# MSP430FR2433_SMD_0402.net
KiCad netlist of a schematic drawn in EAGLE
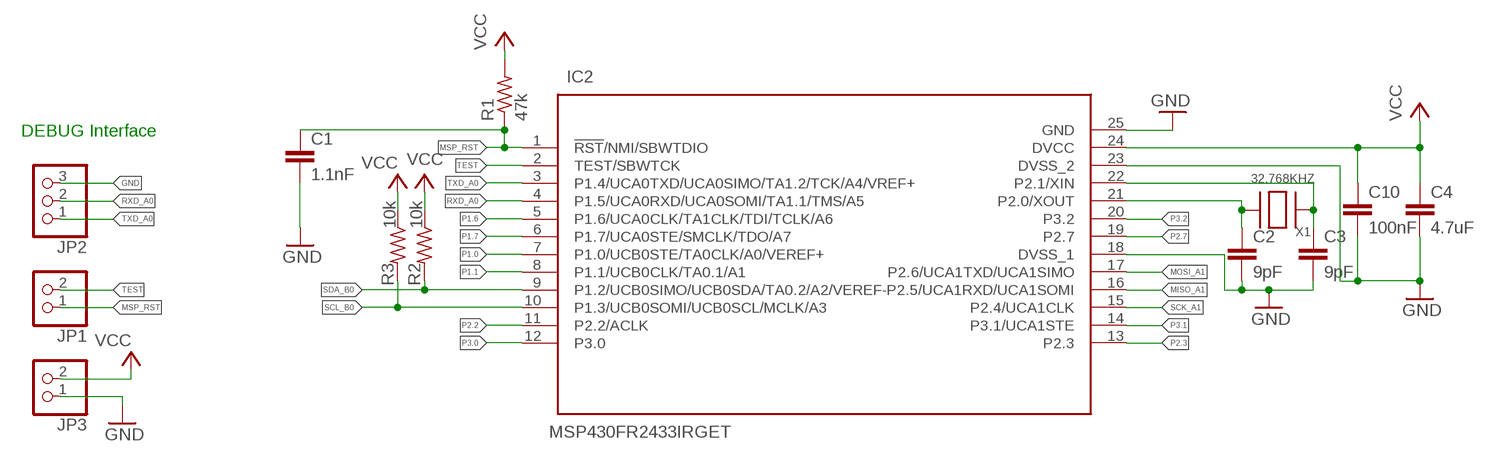
[diagram p0: schematic, sheet 1]

(export (version "E")
  (design (tool "Eeschema 10.0.6"))
  (components
    (comp (ref "C1")
      (value "1.1nF")
      (footprint "eagle-import:C0402")
      (libsource (lib "eagle-import") (part "C-EUC0402"))
    )
    (comp (ref "C2")
      (value "9pF")
      (footprint "eagle-import:C0402")
      (libsource (lib "eagle-import") (part "C-EUC0402"))
    )
    (comp (ref "C3")
      (value "9pF")
      (footprint "eagle-import:C0402")
      (libsource (lib "eagle-import") (part "C-EUC0402"))
    )
    (comp (ref "C4")
      (value "4.7uF")
      (footprint "eagle-import:C0402")
      (libsource (lib "eagle-import") (part "C-EUC0402"))
    )
    (comp (ref "C10")
      (value "100nF")
      (footprint "eagle-import:C0402")
      (libsource (lib "eagle-import") (part "C-EUC0402"))
    )
    (comp (ref "IC2")
      (value "MSP430FR2433IRGET")
      (footprint "eagle-import:QFN50P400X400X100-25N")
      (fields (field (name "MOUSER_PART_NUMBER") "595-SP430FR2433IRGET"))
      (libsource (lib "eagle-import") (part "MSP430FR2433IRGET"))
    )
    (comp (ref "JP1")
      (value "PINHD-1X2")
      (footprint "eagle-import:1X02")
      (libsource (lib "eagle-import") (part "PINHD-1X2"))
    )
    (comp (ref "JP2")
      (value "PINHD-1X3")
      (footprint "eagle-import:1X03")
      (libsource (lib "eagle-import") (part "PINHD-1X3"))
    )
    (comp (ref "JP3")
      (value "PINHD-1X2")
      (footprint "eagle-import:1X02")
      (libsource (lib "eagle-import") (part "PINHD-1X2"))
    )
    (comp (ref "R1")
      (value "47k")
      (footprint "eagle-import:R0402")
      (libsource (lib "eagle-import") (part "R-US_R0402"))
    )
    (comp (ref "R2")
      (value "10k")
      (footprint "eagle-import:R0402")
      (libsource (lib "eagle-import") (part "R-US_R0402"))
    )
    (comp (ref "R3")
      (value "10k")
      (footprint "eagle-import:R0402")
      (libsource (lib "eagle-import") (part "R-US_R0402"))
    )
    (comp (ref "X1")
      (value "32.768KHZ")
      (footprint "eagle-import:XTAL3215")
      (libsource (lib "eagle-import") (part "XTAL-3.2X1.5"))
    )
  )
  (nets
    (net (code "1") (name "GND") (class "Default")
      (node (ref "C1") (pin "2") (pinfunction "2_2") (pintype "passive"))
      (node (ref "C10") (pin "2") (pinfunction "2_2") (pintype "passive"))
      (node (ref "C2") (pin "2") (pinfunction "2_2") (pintype "passive"))
      (node (ref "C3") (pin "2") (pinfunction "2_2") (pintype "passive"))
      (node (ref "C4") (pin "2") (pinfunction "2_2") (pintype "passive"))
      (node (ref "IC2") (pin "18") (pinfunction "DVSS_1_18") (pintype "bidirectional"))
      (node (ref "IC2") (pin "23") (pinfunction "DVSS_2_23") (pintype "bidirectional"))
      (node (ref "IC2") (pin "25") (pinfunction "GND_25") (pintype "bidirectional"))
      (node (ref "JP2") (pin "3") (pinfunction "3_3") (pintype "passive"))
      (node (ref "JP3") (pin "1") (pinfunction "1_1") (pintype "passive"))
    )
    (net (code "2") (name "MISO_A1") (class "Default")
      (node (ref "IC2") (pin "16") (pinfunction "P2.5/UCA1RXD/UCA1SOMI_16") (pintype "bidirectional"))
    )
    (net (code "3") (name "MOSI_A1") (class "Default")
      (node (ref "IC2") (pin "17") (pinfunction "P2.6/UCA1TXD/UCA1SIMO_17") (pintype "bidirectional"))
    )
    (net (code "4") (name "MSP_RST") (class "Default")
      (node (ref "C1") (pin "1") (pinfunction "1_1") (pintype "passive"))
      (node (ref "IC2") (pin "1") (pinfunction "~{RST}/NMI/SBWTDIO_1") (pintype "bidirectional"))
      (node (ref "JP1") (pin "1") (pinfunction "1_1") (pintype "passive"))
      (node (ref "R1") (pin "1") (pinfunction "1_1") (pintype "passive"))
    )
    (net (code "5") (name "Net-(IC2-P2.0{slash}XOUT)") (class "Default")
      (node (ref "C2") (pin "1") (pinfunction "1_1") (pintype "passive"))
      (node (ref "IC2") (pin "21") (pinfunction "P2.0/XOUT_21") (pintype "bidirectional"))
      (node (ref "X1") (pin "P$1") (pinfunction "P$1_P$1") (pintype "bidirectional"))
    )
    (net (code "6") (name "Net-(IC2-P2.1{slash}XIN)") (class "Default")
      (node (ref "C3") (pin "1") (pinfunction "1_1") (pintype "passive"))
      (node (ref "IC2") (pin "22") (pinfunction "P2.1/XIN_22") (pintype "bidirectional"))
      (node (ref "X1") (pin "P$2") (pinfunction "P$2_P$2") (pintype "bidirectional"))
    )
    (net (code "7") (name "P1.0") (class "Default")
      (node (ref "IC2") (pin "7") (pinfunction "P1.0/UCB0STE/TA0CLK/A0/VEREF+_7") (pintype "bidirectional"))
    )
    (net (code "8") (name "P1.1") (class "Default")
      (node (ref "IC2") (pin "8") (pinfunction "P1.1/UCB0CLK/TA0.1/A1_8") (pintype "bidirectional"))
    )
    (net (code "9") (name "P1.6") (class "Default")
      (node (ref "IC2") (pin "5") (pinfunction "P1.6/UCA0CLK/TA1CLK/TDI/TCLK/A6_5") (pintype "bidirectional"))
    )
    (net (code "10") (name "P1.7") (class "Default")
      (node (ref "IC2") (pin "6") (pinfunction "P1.7/UCA0STE/SMCLK/TDO/A7_6") (pintype "bidirectional"))
    )
    (net (code "11") (name "P2.2") (class "Default")
      (node (ref "IC2") (pin "11") (pinfunction "P2.2/ACLK_11") (pintype "bidirectional"))
    )
    (net (code "12") (name "P2.3") (class "Default")
      (node (ref "IC2") (pin "13") (pinfunction "P2.3_13") (pintype "bidirectional"))
    )
    (net (code "13") (name "P2.7") (class "Default")
      (node (ref "IC2") (pin "19") (pinfunction "P2.7_19") (pintype "bidirectional"))
    )
    (net (code "14") (name "P3.0") (class "Default")
      (node (ref "IC2") (pin "12") (pinfunction "P3.0_12") (pintype "bidirectional"))
    )
    (net (code "15") (name "P3.1") (class "Default")
      (node (ref "IC2") (pin "14") (pinfunction "P3.1/UCA1STE_14") (pintype "bidirectional"))
    )
    (net (code "16") (name "P3.2") (class "Default")
      (node (ref "IC2") (pin "20") (pinfunction "P3.2_20") (pintype "bidirectional"))
    )
    (net (code "17") (name "RXD_A0") (class "Default")
      (node (ref "IC2") (pin "4") (pinfunction "P1.5/UCA0RXD/UCA0SOMI/TA1.1/TMS/A5_4") (pintype "bidirectional"))
      (node (ref "JP2") (pin "2") (pinfunction "2_2") (pintype "passive"))
    )
    (net (code "18") (name "SCK_A1") (class "Default")
      (node (ref "IC2") (pin "15") (pinfunction "P2.4/UCA1CLK_15") (pintype "bidirectional"))
    )
    (net (code "19") (name "SCL_B0") (class "Default")
      (node (ref "IC2") (pin "10") (pinfunction "P1.3/UCB0SOMI/UCB0SCL/MCLK/A3_10") (pintype "bidirectional"))
      (node (ref "R3") (pin "2") (pinfunction "2_2") (pintype "passive"))
    )
    (net (code "20") (name "SDA_B0") (class "Default")
      (node (ref "IC2") (pin "9") (pinfunction "P1.2/UCB0SIMO/UCB0SDA/TA0.2/A2/VEREF-_9") (pintype "bidirectional"))
      (node (ref "R2") (pin "2") (pinfunction "2_2") (pintype "passive"))
    )
    (net (code "21") (name "TEST") (class "Default")
      (node (ref "IC2") (pin "2") (pinfunction "TEST/SBWTCK_2") (pintype "bidirectional"))
      (node (ref "JP1") (pin "2") (pinfunction "2_2") (pintype "passive"))
    )
    (net (code "22") (name "TXD_A0") (class "Default")
      (node (ref "IC2") (pin "3") (pinfunction "P1.4/UCA0TXD/UCA0SIMO/TA1.2/TCK/A4/VREF+_3") (pintype "bidirectional"))
      (node (ref "JP2") (pin "1") (pinfunction "1_1") (pintype "passive"))
    )
    (net (code "23") (name "VCC") (class "Default")
      (node (ref "C10") (pin "1") (pinfunction "1_1") (pintype "passive"))
      (node (ref "C4") (pin "1") (pinfunction "1_1") (pintype "passive"))
      (node (ref "IC2") (pin "24") (pinfunction "DVCC_24") (pintype "bidirectional"))
      (node (ref "JP3") (pin "2") (pinfunction "2_2") (pintype "passive"))
      (node (ref "R1") (pin "2") (pinfunction "2_2") (pintype "passive"))
      (node (ref "R2") (pin "1") (pinfunction "1_1") (pintype "passive"))
      (node (ref "R3") (pin "1") (pinfunction "1_1") (pintype "passive"))
    )
  )
)
